# PSU.net
KiCad netlist of a schematic drawn in Altium Designer
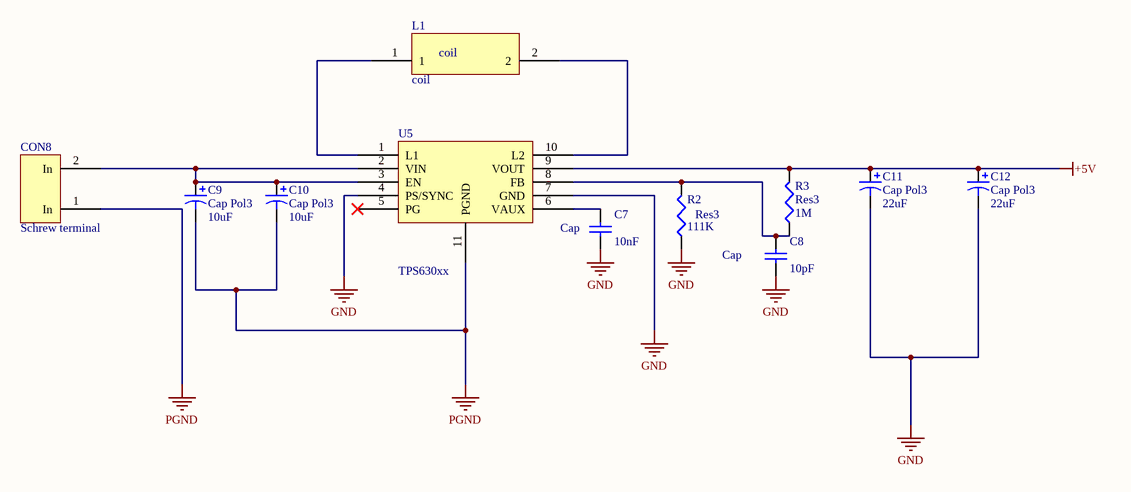
[diagram p0: PSU.SchDoc]

(export (version "E")
  (design (tool "Eeschema 10.0.6"))
  (components
    (comp (ref "C7")
      (value "Cap")
      (footprint "0402")
      (description "Capacitor (Semiconductor SIM Model)")
      (fields (field (name "ALTIUM_VALUE") "10nF") (field (name "PUBLISHER") "Altium Limited"))
      (libsource (lib "Miscellaneous Devices") (part "Cap Semi"))
    )
    (comp (ref "C8")
      (value "Cap")
      (footprint "0402")
      (description "Capacitor (Semiconductor SIM Model)")
      (fields (field (name "ALTIUM_VALUE") "10pF") (field (name "PUBLISHER") "Altium Limited"))
      (libsource (lib "Miscellaneous Devices") (part "Cap Semi"))
    )
    (comp (ref "C9")
      (value "Cap Pol3")
      (footprint "C0805")
      (description "Polarized Capacitor (Surface Mount)")
      (fields (field (name "ALTIUM_VALUE") "10uF") (field (name "PUBLISHER") "Altium Limited"))
      (libsource (lib "Miscellaneous Devices") (part "Cap Pol3"))
    )
    (comp (ref "C10")
      (value "Cap Pol3")
      (footprint "C0805")
      (description "Polarized Capacitor (Surface Mount)")
      (fields (field (name "ALTIUM_VALUE") "10uF") (field (name "PUBLISHER") "Altium Limited"))
      (libsource (lib "Miscellaneous Devices") (part "Cap Pol3"))
    )
    (comp (ref "C11")
      (value "Cap Pol3")
      (footprint "C0805")
      (description "Polarized Capacitor (Surface Mount)")
      (fields (field (name "ALTIUM_VALUE") "22uF") (field (name "PUBLISHER") "Altium Limited"))
      (libsource (lib "Miscellaneous Devices") (part "Cap Pol3"))
    )
    (comp (ref "C12")
      (value "Cap Pol3")
      (footprint "C0805")
      (description "Polarized Capacitor (Surface Mount)")
      (fields (field (name "ALTIUM_VALUE") "22uF") (field (name "PUBLISHER") "Altium Limited"))
      (libsource (lib "Miscellaneous Devices") (part "Cap Pol3"))
    )
    (comp (ref "CON8")
      (value "Schrew terminal")
      (footprint "ScrewTerminal")
      (libsource (lib "ScewTerminal") (part "Schrew terminal"))
    )
    (comp (ref "L1") (value "coil") (footprint "Coil") (libsource (lib "COIL") (part "coil")))
    (comp (ref "R2")
      (value "Res3")
      (footprint "J1-0603")
      (description "Resistor")
      (fields (field (name "ALTIUM_VALUE") "111K") (field (name "PUBLISHER") "Altium Limited"))
      (libsource (lib "Miscellaneous Devices") (part "Res3"))
    )
    (comp (ref "R3")
      (value "Res3")
      (footprint "J1-0603")
      (description "Resistor")
      (fields (field (name "ALTIUM_VALUE") "1M") (field (name "PUBLISHER") "Altium Limited"))
      (libsource (lib "Miscellaneous Devices") (part "Res3"))
    )
    (comp (ref "U5") (value "TPS630xx") (footprint "TPS63061") (libsource (lib "TPS630xx") (part "TPS630xx")))
  )
  (nets
    (net (code "1") (name "+5V") (class "Default")
      (node (ref "C11") (pin "1") (pinfunction "1_1") (pintype "passive"))
      (node (ref "C12") (pin "1") (pinfunction "1_1") (pintype "passive"))
      (node (ref "R3") (pin "2") (pinfunction "2_2") (pintype "passive"))
      (node (ref "U5") (pin "9") (pinfunction "VOUT_9") (pintype "passive"))
    )
    (net (code "2") (name "GND") (class "Default")
      (node (ref "C11") (pin "2") (pinfunction "2_2") (pintype "passive"))
      (node (ref "C12") (pin "2") (pinfunction "2_2") (pintype "passive"))
      (node (ref "C7") (pin "1") (pinfunction "1_1") (pintype "passive"))
      (node (ref "C8") (pin "1") (pinfunction "1_1") (pintype "passive"))
      (node (ref "R2") (pin "1") (pinfunction "1_1") (pintype "passive"))
      (node (ref "U5") (pin "4") (pinfunction "PS/SYNC_4") (pintype "passive"))
      (node (ref "U5") (pin "7") (pinfunction "GND_7") (pintype "passive"))
    )
    (net (code "3") (name "Net-(U5-EN)") (class "Default")
      (node (ref "C10") (pin "1") (pinfunction "1_1") (pintype "passive"))
      (node (ref "C9") (pin "1") (pinfunction "1_1") (pintype "passive"))
      (node (ref "CON8") (pin "2") (pinfunction "In_2") (pintype "passive"))
      (node (ref "U5") (pin "2") (pinfunction "VIN_2") (pintype "passive"))
      (node (ref "U5") (pin "3") (pinfunction "EN_3") (pintype "passive"))
    )
    (net (code "4") (name "Net-(U5-FB)") (class "Default")
      (node (ref "C8") (pin "2") (pinfunction "2_2") (pintype "passive"))
      (node (ref "R2") (pin "2") (pinfunction "2_2") (pintype "passive"))
      (node (ref "R3") (pin "1") (pinfunction "1_1") (pintype "passive"))
      (node (ref "U5") (pin "8") (pinfunction "FB_8") (pintype "passive"))
    )
    (net (code "5") (name "Net-(U5-L1)") (class "Default")
      (node (ref "L1") (pin "1") (pinfunction "1_1") (pintype "power_in"))
      (node (ref "U5") (pin "1") (pinfunction "L1_1") (pintype "passive"))
    )
    (net (code "6") (name "Net-(U5-L2)") (class "Default")
      (node (ref "L1") (pin "2") (pinfunction "2_2") (pintype "power_in"))
      (node (ref "U5") (pin "10") (pinfunction "L2_10") (pintype "passive"))
    )
    (net (code "7") (name "Net-(U5-VAUX)") (class "Default")
      (node (ref "C7") (pin "2") (pinfunction "2_2") (pintype "passive"))
      (node (ref "U5") (pin "6") (pinfunction "VAUX_6") (pintype "passive"))
    )
    (net (code "8") (name "PGND") (class "Default")
      (node (ref "C10") (pin "2") (pinfunction "2_2") (pintype "passive"))
      (node (ref "C9") (pin "2") (pinfunction "2_2") (pintype "passive"))
      (node (ref "CON8") (pin "1") (pinfunction "In_1") (pintype "passive"))
      (node (ref "U5") (pin "11") (pinfunction "PGND_11") (pintype "passive"))
    )
    (net (code "9") (name "unconnected-(U5-PG-Pad5)") (class "Default")
      (node (ref "U5") (pin "5") (pinfunction "PG_5") (pintype "passive+no_connect"))
    )
  )
)
